# ProPrj_BEI_Kimco_Magnetic_Cylindrical_Fr.net
KiCad netlist of a schematic drawn in EasyEDA Pro
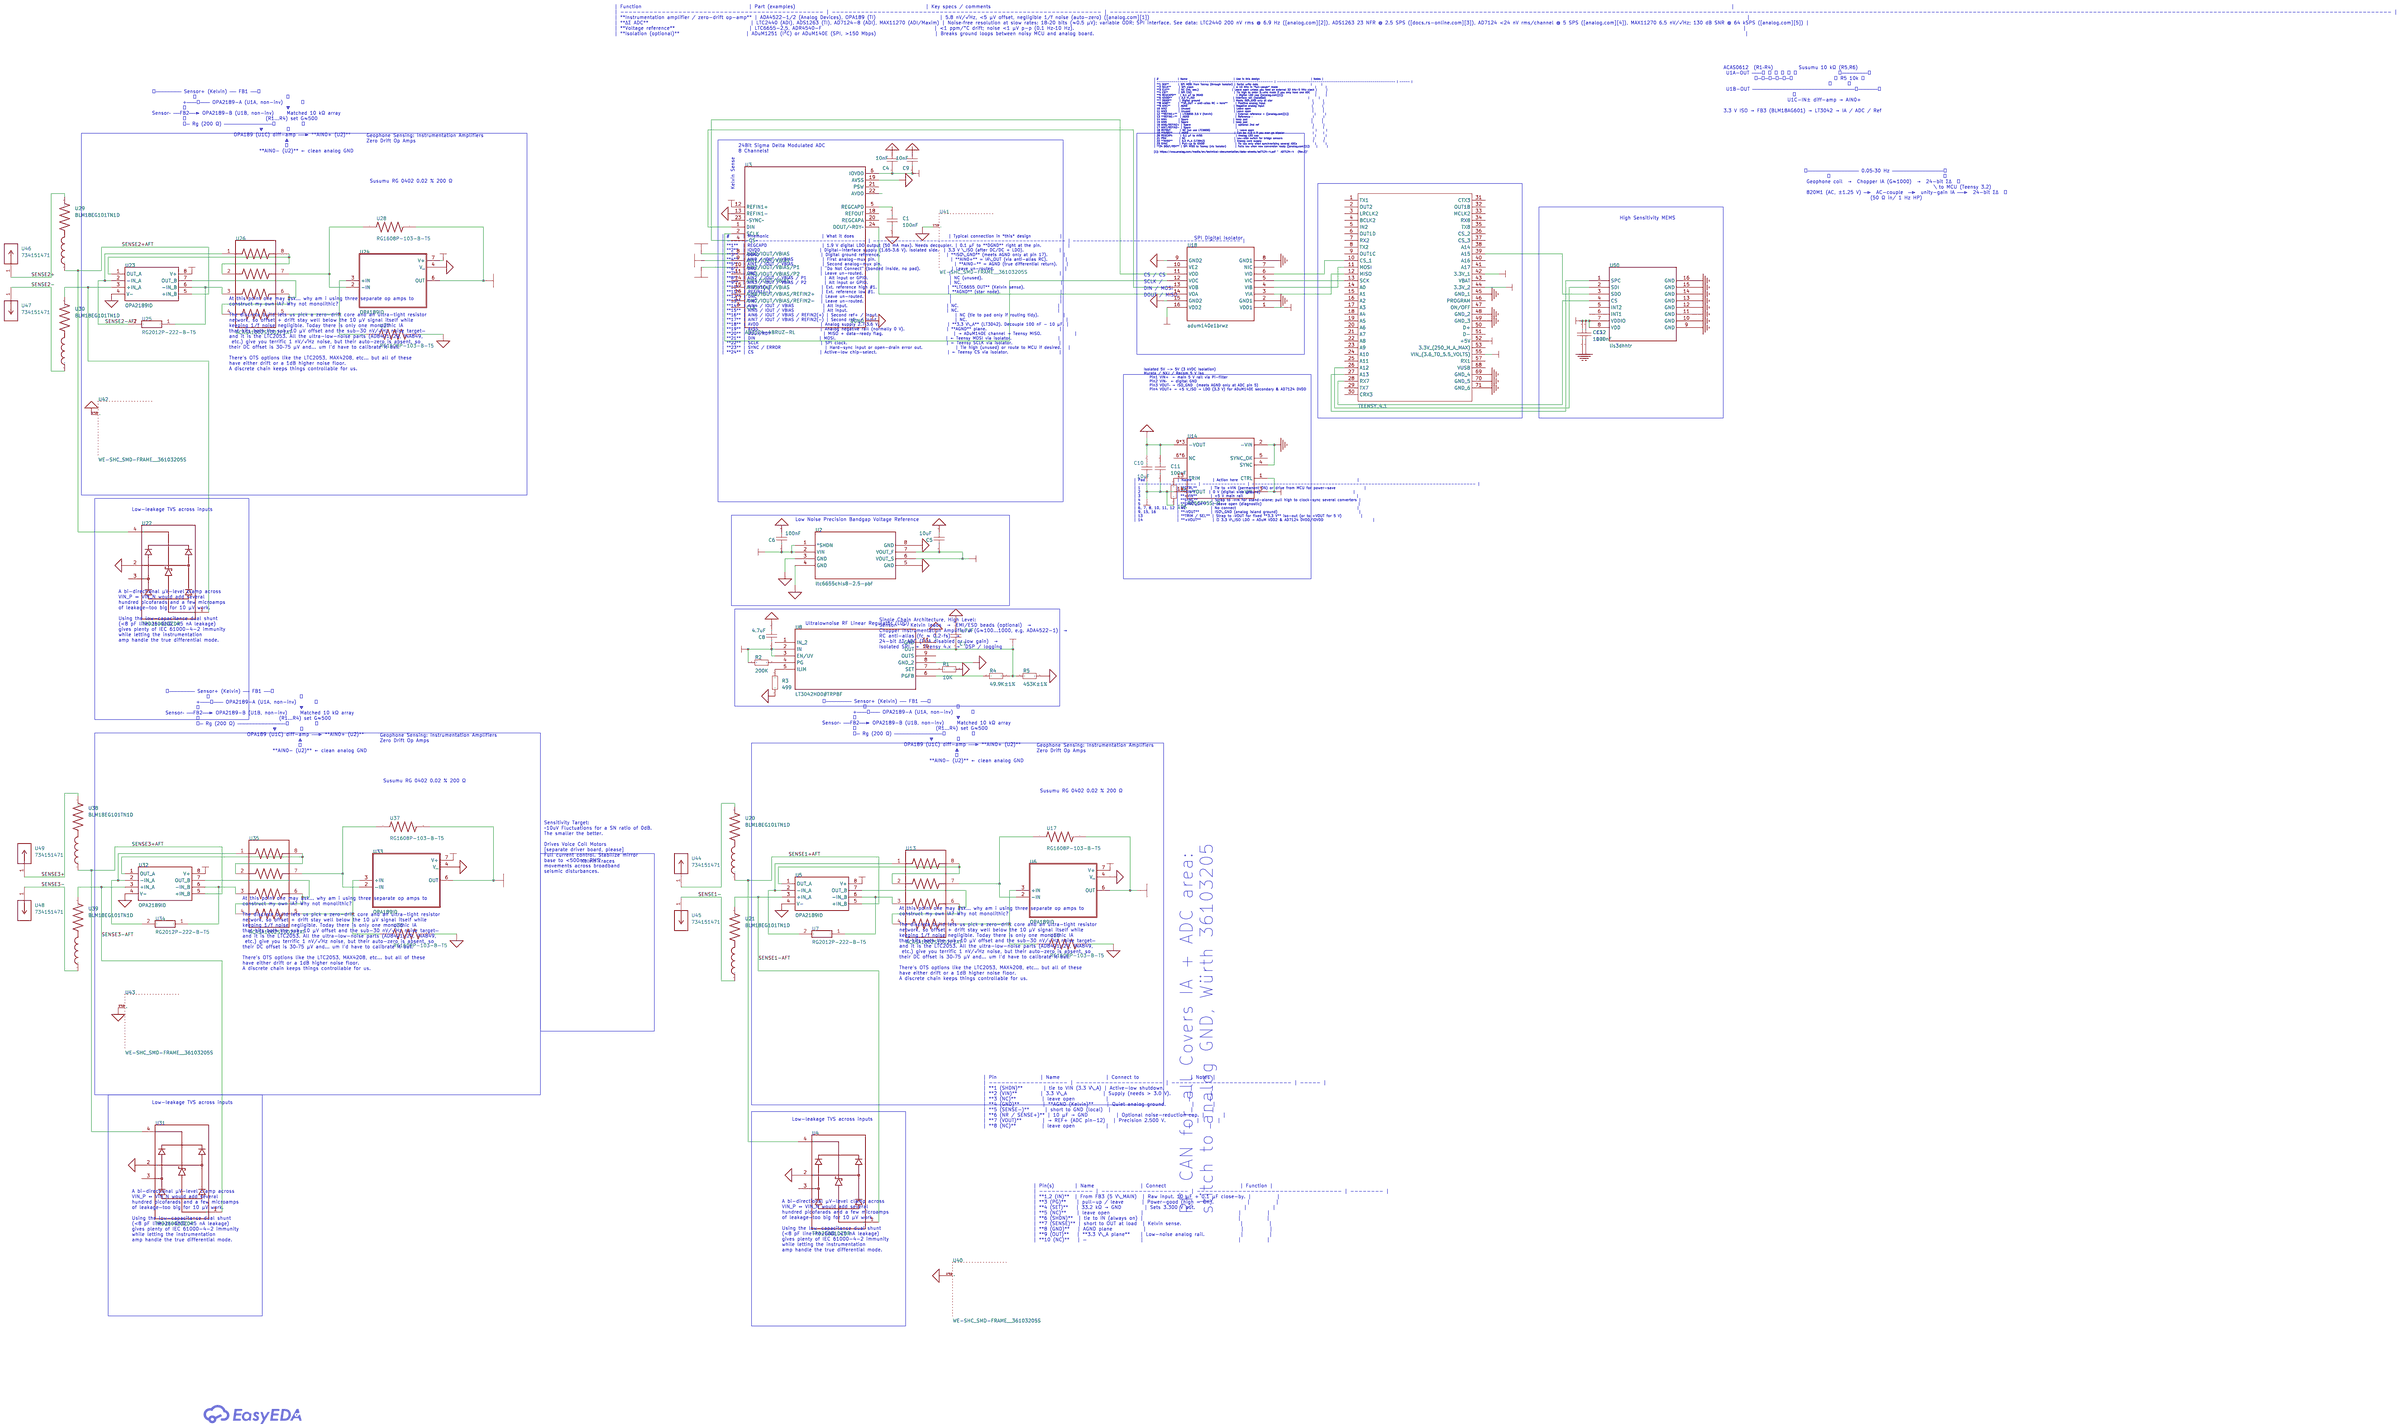
[diagram p0: schematic sheet]

(export (version "E")
  (design (tool "Eeschema 10.0.6"))
  (components
    (comp (ref "C1")
      (value "100nF")
      (footprint "easyedapro:C0603")
      (libsource (lib "easyedapro") (part "CapAcitance"))
    )
    (comp (ref "C4")
      (value "10nF")
      (footprint "easyedapro:C0603")
      (libsource (lib "easyedapro") (part "CapAcitance"))
    )
    (comp (ref "C5")
      (value "10uF")
      (footprint "easyedapro:C0603")
      (libsource (lib "easyedapro") (part "CapAcitance"))
    )
    (comp (ref "C6")
      (value "100nF")
      (footprint "easyedapro:C0603")
      (libsource (lib "easyedapro") (part "CapAcitance"))
    )
    (comp (ref "C7")
      (value "4.7uF")
      (footprint "easyedapro:C0603")
      (libsource (lib "easyedapro") (part "CapAcitance"))
    )
    (comp (ref "C8")
      (value "4.7uF")
      (footprint "easyedapro:C0603")
      (libsource (lib "easyedapro") (part "CapAcitance"))
    )
    (comp (ref "C9")
      (value "10nF")
      (footprint "easyedapro:C0603")
      (libsource (lib "easyedapro") (part "CapAcitance"))
    )
    (comp (ref "C10")
      (value "10uF")
      (footprint "easyedapro:C0603")
      (libsource (lib "easyedapro") (part "CapAcitance"))
    )
    (comp (ref "C11")
      (value "100nF")
      (footprint "easyedapro:C0603")
      (libsource (lib "easyedapro") (part "CapAcitance"))
    )
    (comp (ref "C12")
      (value "100nF")
      (footprint "easyedapro:C0603")
      (libsource (lib "easyedapro") (part "CapAcitance"))
    )
    (comp (ref "C13")
      (value "10uF")
      (footprint "easyedapro:C0603")
      (libsource (lib "easyedapro") (part "CapAcitance"))
    )
    (comp (ref "R1") (value "10K") (footprint "easyedapro:R0603") (libsource (lib "easyedapro") (part "电阻")))
    (comp (ref "R2") (value "200K") (footprint "easyedapro:R0603") (libsource (lib "easyedapro") (part "电阻")))
    (comp (ref "R3") (value "499") (footprint "easyedapro:R0603") (libsource (lib "easyedapro") (part "电阻")))
    (comp (ref "R4")
      (value "49.9K±1%")
      (footprint "easyedapro:R0603")
      (libsource (lib "easyedapro") (part "电阻"))
    )
    (comp (ref "R5")
      (value "453K±1%")
      (footprint "easyedapro:R0603")
      (libsource (lib "easyedapro") (part "电阻"))
    )
    (comp (ref "R6") (value "10K") (footprint "easyedapro:R0603") (libsource (lib "easyedapro") (part "电阻")))
    (comp (ref "U2")
      (value "ltc6655chls8-2.5-pbf")
      (footprint "easyedapro:LTC6655CHLS8-2.5-PBF")
      (libsource (lib "easyedapro") (part "ltc6655chls8-2.5-pbf"))
    )
    (comp (ref "U3")
      (value "AD7124-4BRUZ-RL")
      (footprint "easyedapro:SOP65P640X120-24N")
      (libsource (lib "easyedapro") (part "AD7124-4BRUZ-RL"))
    )
    (comp (ref "U4")
      (value "TPD2E001DZDR")
      (footprint "easyedapro:SOT192P237X122-4N")
      (libsource (lib "easyedapro") (part "TPD2E001DZDR"))
    )
    (comp (ref "U5")
      (value "OPA2189ID")
      (footprint "easyedapro:SOIC127P600X175-8N")
      (description "2 Op Amps in 1. Zero Drift.")
      (libsource (lib "easyedapro") (part "OPA2189ID"))
    )
    (comp (ref "U6")
      (value "OPA189ID")
      (footprint "easyedapro:SOIC127P599X175-8N")
      (libsource (lib "easyedapro") (part "OPA189ID"))
    )
    (comp (ref "U7")
      (value "RG2012P-222-B-T5")
      (footprint "easyedapro:RESC2012X50N")
      (libsource (lib "easyedapro") (part "RG2012P-222-B-T5"))
    )
    (comp (ref "U8")
      (value "LT3042HDD#TRPBF")
      (footprint "easyedapro:DFN-10_DD")
      (description "LDO")
      (libsource (lib "easyedapro") (part "LT3042HDD#TRPBF"))
    )
    (comp (ref "U13")
      (value "ACASA1002S1002P1AT")
      (footprint "easyedapro:RESCAXS80P320X150X55-8N")
      (libsource (lib "easyedapro") (part "ACASA1002S1002P1AT"))
    )
    (comp (ref "U14")
      (value "R05CT05S-R")
      (footprint "easyedapro:SOIC127P1030X265-16N")
      (description "Isolated 5 V→5 V DC/DC")
      (libsource (lib "easyedapro") (part "R05CT05S-R"))
    )
    (comp (ref "U16")
      (value "RG1608P-103-B-T5")
      (footprint "easyedapro:RESC1608X50N")
      (libsource (lib "easyedapro") (part "RG1608P-103-B-T5"))
    )
    (comp (ref "U17")
      (value "RG1608P-103-B-T5")
      (footprint "easyedapro:RESC1608X50N")
      (libsource (lib "easyedapro") (part "RG1608P-103-B-T5"))
    )
    (comp (ref "U18")
      (value "adum140e1brwz")
      (footprint "easyedapro:ADUM140E1BRWZ")
      (libsource (lib "easyedapro") (part "adum140e1brwz"))
    )
    (comp (ref "U20")
      (value "BLM18EG101TN1D")
      (footprint "easyedapro:BEADC1608X65N")
      (description "Ferrite Bead")
      (libsource (lib "easyedapro") (part "BLM18EG101TN1D"))
    )
    (comp (ref "U21")
      (value "BLM18EG101TN1D")
      (footprint "easyedapro:BEADC1608X65N")
      (description "Ferrite Bead")
      (libsource (lib "easyedapro") (part "BLM18EG101TN1D"))
    )
    (comp (ref "U22")
      (value "TPD2E001DZDR")
      (footprint "easyedapro:SOT192P237X122-4N")
      (libsource (lib "easyedapro") (part "TPD2E001DZDR"))
    )
    (comp (ref "U23")
      (value "OPA2189ID")
      (footprint "easyedapro:SOIC127P600X175-8N")
      (description "2 Op Amps in 1. Zero Drift.")
      (libsource (lib "easyedapro") (part "OPA2189ID"))
    )
    (comp (ref "U24")
      (value "OPA189ID")
      (footprint "easyedapro:SOIC127P599X175-8N")
      (libsource (lib "easyedapro") (part "OPA189ID"))
    )
    (comp (ref "U25")
      (value "RG2012P-222-B-T5")
      (footprint "easyedapro:RESC2012X50N")
      (libsource (lib "easyedapro") (part "RG2012P-222-B-T5"))
    )
    (comp (ref "U26")
      (value "ACASA1002S1002P1AT")
      (footprint "easyedapro:RESCAXS80P320X150X55-8N")
      (libsource (lib "easyedapro") (part "ACASA1002S1002P1AT"))
    )
    (comp (ref "U27")
      (value "RG1608P-103-B-T5")
      (footprint "easyedapro:RESC1608X50N")
      (libsource (lib "easyedapro") (part "RG1608P-103-B-T5"))
    )
    (comp (ref "U28")
      (value "RG1608P-103-B-T5")
      (footprint "easyedapro:RESC1608X50N")
      (libsource (lib "easyedapro") (part "RG1608P-103-B-T5"))
    )
    (comp (ref "U29")
      (value "BLM18EG101TN1D")
      (footprint "easyedapro:BEADC1608X65N")
      (description "Ferrite Bead")
      (libsource (lib "easyedapro") (part "BLM18EG101TN1D"))
    )
    (comp (ref "U30")
      (value "BLM18EG101TN1D")
      (footprint "easyedapro:BEADC1608X65N")
      (description "Ferrite Bead")
      (libsource (lib "easyedapro") (part "BLM18EG101TN1D"))
    )
    (comp (ref "U31")
      (value "TPD2E001DZDR")
      (footprint "easyedapro:SOT192P237X122-4N")
      (libsource (lib "easyedapro") (part "TPD2E001DZDR"))
    )
    (comp (ref "U32")
      (value "OPA2189ID")
      (footprint "easyedapro:SOIC127P600X175-8N")
      (description "2 Op Amps in 1. Zero Drift.")
      (libsource (lib "easyedapro") (part "OPA2189ID"))
    )
    (comp (ref "U33")
      (value "OPA189ID")
      (footprint "easyedapro:SOIC127P599X175-8N")
      (libsource (lib "easyedapro") (part "OPA189ID"))
    )
    (comp (ref "U34")
      (value "RG2012P-222-B-T5")
      (footprint "easyedapro:RESC2012X50N")
      (libsource (lib "easyedapro") (part "RG2012P-222-B-T5"))
    )
    (comp (ref "U35")
      (value "ACASA1002S1002P1AT")
      (footprint "easyedapro:RESCAXS80P320X150X55-8N")
      (libsource (lib "easyedapro") (part "ACASA1002S1002P1AT"))
    )
    (comp (ref "U36")
      (value "RG1608P-103-B-T5")
      (footprint "easyedapro:RESC1608X50N")
      (libsource (lib "easyedapro") (part "RG1608P-103-B-T5"))
    )
    (comp (ref "U37")
      (value "RG1608P-103-B-T5")
      (footprint "easyedapro:RESC1608X50N")
      (libsource (lib "easyedapro") (part "RG1608P-103-B-T5"))
    )
    (comp (ref "U38")
      (value "BLM18EG101TN1D")
      (footprint "easyedapro:BEADC1608X65N")
      (description "Ferrite Bead")
      (libsource (lib "easyedapro") (part "BLM18EG101TN1D"))
    )
    (comp (ref "U39")
      (value "BLM18EG101TN1D")
      (footprint "easyedapro:BEADC1608X65N")
      (description "Ferrite Bead")
      (libsource (lib "easyedapro") (part "BLM18EG101TN1D"))
    )
    (comp (ref "U40")
      (value "WE-SHC_SMD-FRAME__36103205S")
      (footprint "easyedapro:WE-SHC_SMD-FRAME_36103205S")
      (libsource (lib "easyedapro") (part "WE-SHC_SMD-FRAME__36103205S"))
    )
    (comp (ref "U41")
      (value "WE-SHC_SMD-FRAME__36103205S")
      (footprint "easyedapro:WE-SHC_SMD-FRAME_36103205S")
      (libsource (lib "easyedapro") (part "WE-SHC_SMD-FRAME__36103205S"))
    )
    (comp (ref "U42")
      (value "WE-SHC_SMD-FRAME__36103205S")
      (footprint "easyedapro:WE-SHC_SMD-FRAME_36103205S")
      (libsource (lib "easyedapro") (part "WE-SHC_SMD-FRAME__36103205S"))
    )
    (comp (ref "U43")
      (value "WE-SHC_SMD-FRAME__36103205S")
      (footprint "easyedapro:WE-SHC_SMD-FRAME_36103205S")
      (libsource (lib "easyedapro") (part "WE-SHC_SMD-FRAME__36103205S"))
    )
    (comp (ref "U44")
      (value "734151471")
      (footprint "easyedapro:CONN_734151471_MOL")
      (libsource (lib "easyedapro") (part "734151471"))
    )
    (comp (ref "U45")
      (value "734151471")
      (footprint "easyedapro:CONN_734151471_MOL")
      (libsource (lib "easyedapro") (part "734151471"))
    )
    (comp (ref "U46")
      (value "734151471")
      (footprint "easyedapro:CONN_734151471_MOL")
      (libsource (lib "easyedapro") (part "734151471"))
    )
    (comp (ref "U47")
      (value "734151471")
      (footprint "easyedapro:CONN_734151471_MOL")
      (libsource (lib "easyedapro") (part "734151471"))
    )
    (comp (ref "U48")
      (value "734151471")
      (footprint "easyedapro:CONN_734151471_MOL")
      (libsource (lib "easyedapro") (part "734151471"))
    )
    (comp (ref "U49")
      (value "734151471")
      (footprint "easyedapro:CONN_734151471_MOL")
      (libsource (lib "easyedapro") (part "734151471"))
    )
    (comp (ref "U50")
      (value "lis3dhhtr")
      (footprint "easyedapro:LIS3DHHTR")
      (libsource (lib "easyedapro") (part "lis3dhhtr"))
    )
    (comp (ref "U51")
      (value "TEENSY_4.1")
      (footprint "easyedapro:TEENSY41")
      (libsource (lib "easyedapro") (part "TEENSY_4.1"))
    )
  )
  (nets
    (net (code "1") (name "+2.5V") (class "Default")
      (node (ref "C5") (pin "2") (pinfunction "2_2") (pintype "input"))
      (node (ref "U2") (pin "6") (pinfunction "VOUT_S_6") (pintype "unspecified"))
      (node (ref "U2") (pin "7") (pinfunction "VOUT_F_7") (pintype "unspecified"))
      (node (ref "U3") (pin "12") (pinfunction "REFIN1+_12") (pintype "input"))
    )
    (net (code "2") (name "+3.3VANALOGSIDE") (class "Default")
      (node (ref "C4") (pin "1") (pinfunction "1_1") (pintype "input"))
      (node (ref "C6") (pin "2") (pinfunction "2_2") (pintype "input"))
      (node (ref "C7") (pin "2") (pinfunction "2_2") (pintype "input"))
      (node (ref "C9") (pin "1") (pinfunction "1_1") (pintype "input"))
      (node (ref "R4") (pin "2") (pinfunction "2_2") (pintype "input"))
      (node (ref "R5") (pin "1") (pinfunction "1_1") (pintype "input"))
      (node (ref "U18") (pin "16") (pinfunction "VDD2_16") (pintype "unspecified"))
      (node (ref "U2") (pin "1") (pinfunction "*SHDN_1") (pintype "unspecified"))
      (node (ref "U2") (pin "2") (pinfunction "VIN_2") (pintype "unspecified"))
      (node (ref "U23") (pin "8") (pinfunction "V+_8") (pintype "bidirectional"))
      (node (ref "U24") (pin "7") (pinfunction "V+_7") (pintype "unspecified"))
      (node (ref "U3") (pin "6") (pinfunction "IOVDD_6") (pintype "unspecified"))
      (node (ref "U32") (pin "8") (pinfunction "V+_8") (pintype "bidirectional"))
      (node (ref "U33") (pin "7") (pinfunction "V+_7") (pintype "unspecified"))
      (node (ref "U5") (pin "8") (pinfunction "V+_8") (pintype "bidirectional"))
      (node (ref "U6") (pin "7") (pinfunction "V+_7") (pintype "unspecified"))
      (node (ref "U8") (pin "10") (pinfunction "OUT_10") (pintype "output"))
    )
    (net (code "3") (name "+3.3V_D") (class "Default")
      (node (ref "C12") (pin "2") (pinfunction "2_2") (pintype "input"))
      (node (ref "C13") (pin "2") (pinfunction "2_2") (pintype "input"))
      (node (ref "U18") (pin "1") (pinfunction "VDD1_1") (pintype "unspecified"))
      (node (ref "U50") (pin "7") (pinfunction "VDDIO_7") (pintype "unspecified"))
      (node (ref "U50") (pin "8") (pinfunction "VDD_8") (pintype "unspecified"))
      (node (ref "U51") (pin "42") (pinfunction "3.3V_1_42") (pintype "bidirectional"))
      (node (ref "U51") (pin "44") (pinfunction "3.3V_2_44") (pintype "bidirectional"))
    )
    (net (code "4") (name "+5V_D") (class "Default")
      (node (ref "U14") (pin "1") (pinfunction "CTRL_1") (pintype "input"))
      (node (ref "U14") (pin "3") (pinfunction "+VIN_3") (pintype "input"))
      (node (ref "U51") (pin "52") (pinfunction "+5V_52") (pintype "bidirectional"))
      (node (ref "U51") (pin "55") (pinfunction "VIN_(3.6_TO_5.5_VOLTS)_55") (pintype "bidirectional"))
    )
    (net (code "5") (name "+5V_ISO") (class "Default")
      (node (ref "C10") (pin "1") (pinfunction "1_1") (pintype "input"))
      (node (ref "C11") (pin "1") (pinfunction "1_1") (pintype "input"))
      (node (ref "C8") (pin "2") (pinfunction "2_2") (pintype "input"))
      (node (ref "R2") (pin "1") (pinfunction "1_1") (pintype "input"))
      (node (ref "R6") (pin "1") (pinfunction "1_1") (pintype "input"))
      (node (ref "U14") (pin "14") (pinfunction "+VOUT_14") (pintype "output"))
      (node (ref "U8") (pin "2") (pinfunction "IN_2") (pintype "input"))
      (node (ref "U8") (pin "3") (pinfunction "EN/UV_3") (pintype "output"))
    )
    (net (code "6") (name "/SENSE1+AFT") (class "Default")
      (node (ref "U20") (pin "1") (pinfunction "1_1") (pintype "unspecified"))
      (node (ref "U4") (pin "4") (pinfunction "VCC_4") (pintype "unspecified"))
      (node (ref "U5") (pin "5") (pinfunction "+IN_B_5") (pintype "bidirectional"))
    )
    (net (code "7") (name "/SENSE1-") (class "Default")
      (node (ref "U21") (pin "1") (pinfunction "1_1") (pintype "unspecified"))
      (node (ref "U45") (pin "1") (pinfunction "1_1") (pintype "unspecified"))
    )
    (net (code "8") (name "/SENSE1-AFT") (class "Default")
      (node (ref "U21") (pin "2") (pinfunction "2_2") (pintype "unspecified"))
      (node (ref "U4") (pin "1") (pinfunction "GND_1") (pintype "unspecified"))
      (node (ref "U5") (pin "3") (pinfunction "+IN_A_3") (pintype "bidirectional"))
    )
    (net (code "9") (name "/SENSE2+") (class "Default")
      (node (ref "U29") (pin "2") (pinfunction "2_2") (pintype "unspecified"))
      (node (ref "U46") (pin "1") (pinfunction "1_1") (pintype "unspecified"))
    )
    (net (code "10") (name "/SENSE2+AFT") (class "Default")
      (node (ref "U22") (pin "4") (pinfunction "VCC_4") (pintype "unspecified"))
      (node (ref "U23") (pin "5") (pinfunction "+IN_B_5") (pintype "bidirectional"))
      (node (ref "U29") (pin "1") (pinfunction "1_1") (pintype "unspecified"))
    )
    (net (code "11") (name "/SENSE2-") (class "Default")
      (node (ref "U30") (pin "1") (pinfunction "1_1") (pintype "unspecified"))
      (node (ref "U47") (pin "1") (pinfunction "1_1") (pintype "unspecified"))
    )
    (net (code "12") (name "/SENSE2-AFT") (class "Default")
      (node (ref "U23") (pin "2") (pinfunction "-IN_A_2") (pintype "bidirectional"))
      (node (ref "U25") (pin "2") (pinfunction "2_2") (pintype "bidirectional"))
      (node (ref "U26") (pin "1") (pinfunction "1_1") (pintype "unspecified"))
    )
    (net (code "13") (name "/SENSE3+") (class "Default")
      (node (ref "U38") (pin "2") (pinfunction "2_2") (pintype "unspecified"))
      (node (ref "U49") (pin "1") (pinfunction "1_1") (pintype "unspecified"))
    )
    (net (code "14") (name "/SENSE3+AFT") (class "Default")
      (node (ref "U31") (pin "4") (pinfunction "VCC_4") (pintype "unspecified"))
      (node (ref "U32") (pin "5") (pinfunction "+IN_B_5") (pintype "bidirectional"))
      (node (ref "U38") (pin "1") (pinfunction "1_1") (pintype "unspecified"))
    )
    (net (code "15") (name "/SENSE3-") (class "Default")
      (node (ref "U39") (pin "1") (pinfunction "1_1") (pintype "unspecified"))
      (node (ref "U48") (pin "1") (pinfunction "1_1") (pintype "unspecified"))
    )
    (net (code "16") (name "/SENSE3-AFT") (class "Default")
      (node (ref "U31") (pin "1") (pinfunction "GND_1") (pintype "unspecified"))
      (node (ref "U32") (pin "3") (pinfunction "+IN_A_3") (pintype "bidirectional"))
      (node (ref "U39") (pin "2") (pinfunction "2_2") (pintype "unspecified"))
    )
    (net (code "17") (name "AGND") (class "Default")
      (node (ref "C1") (pin "2") (pinfunction "2_2") (pintype "input"))
      (node (ref "C10") (pin "2") (pinfunction "2_2") (pintype "input"))
      (node (ref "C11") (pin "2") (pinfunction "2_2") (pintype "input"))
      (node (ref "C4") (pin "2") (pinfunction "2_2") (pintype "input"))
      (node (ref "C5") (pin "1") (pinfunction "1_1") (pintype "input"))
      (node (ref "C6") (pin "1") (pinfunction "1_1") (pintype "input"))
      (node (ref "C7") (pin "1") (pinfunction "1_1") (pintype "input"))
      (node (ref "C8") (pin "1") (pinfunction "1_1") (pintype "input"))
      (node (ref "C9") (pin "2") (pinfunction "2_2") (pintype "input"))
      (node (ref "R1") (pin "2") (pinfunction "2_2") (pintype "input"))
      (node (ref "R3") (pin "1") (pinfunction "1_1") (pintype "input"))
      (node (ref "R5") (pin "2") (pinfunction "2_2") (pintype "input"))
      (node (ref "U14") (pin "9*3") (pinfunction "-VOUT_9*3") (pintype "output"))
      (node (ref "U16") (pin "2") (pinfunction "2_2") (pintype "unspecified"))
      (node (ref "U18") (pin "15") (pinfunction "GND2_15") (pintype "unspecified"))
      (node (ref "U18") (pin "9") (pinfunction "GND2_9") (pintype "unspecified"))
      (node (ref "U2") (pin "3") (pinfunction "GND_3") (pintype "unspecified"))
      (node (ref "U2") (pin "4") (pinfunction "GND_4") (pintype "unspecified"))
      (node (ref "U2") (pin "5") (pinfunction "GND_5") (pintype "unspecified"))
      (node (ref "U2") (pin "8") (pinfunction "GND_8") (pintype "unspecified"))
      (node (ref "U22") (pin "2") (pinfunction "IO1_2") (pintype "bidirectional"))
      (node (ref "U23") (pin "4") (pinfunction "V-_4") (pintype "bidirectional"))
      (node (ref "U24") (pin "4") (pinfunction "V__4") (pintype "unspecified"))
      (node (ref "U27") (pin "2") (pinfunction "2_2") (pintype "unspecified"))
      (node (ref "U3") (pin "13") (pinfunction "REFIN1-_13") (pintype "input"))
      (node (ref "U3") (pin "19") (pinfunction "AVSS_19") (pintype "unspecified"))
      (node (ref "U3") (pin "7") (pinfunction "DGND_7") (pintype "unspecified"))
      (node (ref "U31") (pin "2") (pinfunction "IO1_2") (pintype "bidirectional"))
      (node (ref "U32") (pin "4") (pinfunction "V-_4") (pintype "bidirectional"))
      (node (ref "U33") (pin "4") (pinfunction "V__4") (pintype "unspecified"))
      (node (ref "U36") (pin "2") (pinfunction "2_2") (pintype "unspecified"))
      (node (ref "U4") (pin "2") (pinfunction "IO1_2") (pintype "bidirectional"))
      (node (ref "U40") (pin "1*16") (pinfunction "GND_1*16") (pintype "unspecified"))
      (node (ref "U41") (pin "1*16") (pinfunction "GND_1*16") (pintype "unspecified"))
      (node (ref "U42") (pin "1*16") (pinfunction "GND_1*16") (pintype "unspecified"))
      (node (ref "U43") (pin "1*16") (pinfunction "GND_1*16") (pintype "unspecified"))
      (node (ref "U5") (pin "4") (pinfunction "V-_4") (pintype "bidirectional"))
      (node (ref "U6") (pin "4") (pinfunction "V__4") (pintype "unspecified"))
      (node (ref "U8") (pin "11") (pinfunction "GND_11") (pintype "unspecified"))
      (node (ref "U8") (pin "8") (pinfunction "GND_2_8") (pintype "unspecified"))
    )
    (net (code "18") (name "DGND") (class "Default")
      (node (ref "C12") (pin "1") (pinfunction "1_1") (pintype "input"))
      (node (ref "C13") (pin "1") (pinfunction "1_1") (pintype "input"))
      (node (ref "U14") (pin "2") (pinfunction "-VIN_2") (pintype "input"))
      (node (ref "U14") (pin "4") (pinfunction "SYNC_4") (pintype "input"))
      (node (ref "U18") (pin "2") (pinfunction "GND1_2") (pintype "unspecified"))
      (node (ref "U18") (pin "8") (pinfunction "GND1_8") (pintype "unspecified"))
      (node (ref "U50") (pin "10") (pinfunction "GND_10") (pintype "unspecified"))
      (node (ref "U50") (pin "11") (pinfunction "GND_11") (pintype "unspecified"))
      (node (ref "U50") (pin "12") (pinfunction "GND_12") (pintype "unspecified"))
      (node (ref "U50") (pin "13") (pinfunction "GND_13") (pintype "unspecified"))
      (node (ref "U50") (pin "14") (pinfunction "GND_14") (pintype "unspecified"))
      (node (ref "U50") (pin "15") (pinfunction "GND_15") (pintype "unspecified"))
      (node (ref "U50") (pin "16") (pinfunction "GND_16") (pintype "unspecified"))
      (node (ref "U50") (pin "9") (pinfunction "GND_9") (pintype "unspecified"))
      (node (ref "U51") (pin "45") (pinfunction "GND_1_45") (pintype "bidirectional"))
      (node (ref "U51") (pin "48") (pinfunction "GND_2_48") (pintype "bidirectional"))
      (node (ref "U51") (pin "49") (pinfunction "GND_3_49") (pintype "bidirectional"))
      (node (ref "U51") (pin "69") (pinfunction "GND_4_69") (pintype "bidirectional"))
      (node (ref "U51") (pin "70") (pinfunction "GND_5_70") (pintype "bidirectional"))
      (node (ref "U51") (pin "71") (pinfunction "GND_6_71") (pintype "bidirectional"))
    )
    (net (code "19") (name "Net-(U3-REGCAPD)") (class "Default")
      (node (ref "C1") (pin "1") (pinfunction "1_1") (pintype "input"))
      (node (ref "U3") (pin "5") (pinfunction "REGCAPD_5") (pintype "output"))
    )
    (net (code "20") (name "Net-(U5--IN_A)") (class "Default")
      (node (ref "U13") (pin "1") (pinfunction "1_1") (pintype "unspecified"))
      (node (ref "U5") (pin "2") (pinfunction "-IN_A_2") (pintype "bidirectional"))
      (node (ref "U7") (pin "2") (pinfunction "2_2") (pintype "bidirectional"))
    )
    (net (code "21") (name "Net-(U5--IN_B)") (class "Default")
      (node (ref "U13") (pin "3") (pinfunction "3_3") (pintype "unspecified"))
      (node (ref "U5") (pin "6") (pinfunction "-IN_B_6") (pintype "bidirectional"))
      (node (ref "U7") (pin "1") (pinfunction "1_1") (pintype "bidirectional"))
    )
    (net (code "22") (name "Net-(U5-OUT_A)") (class "Default")
      (node (ref "U13") (pin "2") (pinfunction "2_2") (pintype "unspecified"))
      (node (ref "U13") (pin "8") (pinfunction "8_8") (pintype "unspecified"))
      (node (ref "U5") (pin "1") (pinfunction "OUT_A_1") (pintype "bidirectional"))
    )
    (net (code "23") (name "Net-(U5-OUT_B)") (class "Default")
      (node (ref "U13") (pin "4") (pinfunction "4_4") (pintype "unspecified"))
      (node (ref "U13") (pin "6") (pinfunction "6_6") (pintype "unspecified"))
      (node (ref "U5") (pin "7") (pinfunction "OUT_B_7") (pintype "bidirectional"))
    )
    (net (code "24") (name "Net-(U6-+IN)") (class "Default")
      (node (ref "U13") (pin "5") (pinfunction "5_5") (pintype "unspecified"))
      (node (ref "U16") (pin "1") (pinfunction "1_1") (pintype "unspecified"))
      (node (ref "U6") (pin "3") (pinfunction "+IN_3") (pintype "input"))
    )
    (net (code "25") (name "Net-(U6--IN)") (class "Default")
      (node (ref "U13") (pin "7") (pinfunction "7_7") (pintype "unspecified"))
      (node (ref "U17") (pin "1") (pinfunction "1_1") (pintype "unspecified"))
      (node (ref "U6") (pin "2") (pinfunction "-IN_2") (pintype "input"))
    )
    (net (code "26") (name "Net-(U8-ILIM)") (class "Default")
      (node (ref "R3") (pin "2") (pinfunction "2_2") (pintype "input"))
      (node (ref "U8") (pin "5") (pinfunction "ILIM_5") (pintype "unspecified"))
    )
    (net (code "27") (name "Net-(U8-PG)") (class "Default")
      (node (ref "R2") (pin "2") (pinfunction "2_2") (pintype "input"))
      (node (ref "U8") (pin "4") (pinfunction "PG_4") (pintype "unspecified"))
    )
    (net (code "28") (name "Net-(U8-PGFB)") (class "Default")
      (node (ref "R4") (pin "1") (pinfunction "1_1") (pintype "input"))
      (node (ref "U8") (pin "6") (pinfunction "PGFB_6") (pintype "unspecified"))
    )
    (net (code "29") (name "Net-(U8-SET)") (class "Default")
      (node (ref "R1") (pin "1") (pinfunction "1_1") (pintype "input"))
      (node (ref "U8") (pin "7") (pinfunction "SET_7") (pintype "input"))
    )
    (net (code "30") (name "Net-(U14-TRIM)") (class "Default")
      (node (ref "R6") (pin "2") (pinfunction "2_2") (pintype "input"))
      (node (ref "U14") (pin "13") (pinfunction "TRIM_13") (pintype "unspecified"))
    )
    (net (code "31") (name "Net-(U18-VIA)") (class "Default")
      (node (ref "U18") (pin "3") (pinfunction "VIA_3") (pintype "unspecified"))
      (node (ref "U51") (pin "12") (pinfunction "MISO_12") (pintype "bidirectional"))
    )
    (net (code "32") (name "Net-(U18-VIB)") (class "Default")
      (node (ref "U18") (pin "4") (pinfunction "VIB_4") (pintype "unspecified"))
      (node (ref "U51") (pin "11") (pinfunction "MOSI_11") (pintype "bidirectional"))
    )
    (net (code "33") (name "Net-(U18-VIC)") (class "Default")
      (node (ref "U18") (pin "5") (pinfunction "VIC_5") (pintype "unspecified"))
      (node (ref "U51") (pin "13") (pinfunction "SCK_13") (pintype "bidirectional"))
    )
    (net (code "34") (name "Net-(U18-VID)") (class "Default")
      (node (ref "U18") (pin "6") (pinfunction "VID_6") (pintype "unspecified"))
      (node (ref "U51") (pin "10") (pinfunction "CS_1_10") (pintype "bidirectional"))
    )
    (net (code "35") (name "Net-(U18-VOA)") (class "Default")
      (node (ref "U18") (pin "14") (pinfunction "VOA_14") (pintype "unspecified"))
      (node (ref "U3") (pin "24") (pinfunction "DOUT/~RDY~_24") (pintype "output"))
    )
    (net (code "36") (name "Net-(U18-VOB)") (class "Default")
      (node (ref "U18") (pin "13") (pinfunction "VOB_13") (pintype "unspecified"))
      (node (ref "U3") (pin "1") (pinfunction "DIN_1") (pintype "input"))
    )
    (net (code "37") (name "Net-(U18-VOC)") (class "Default")
      (node (ref "U18") (pin "12") (pinfunction "VOC_12") (pintype "unspecified"))
      (node (ref "U3") (pin "2") (pinfunction "SCLK_2") (pintype "input"))
    )
    (net (code "38") (name "Net-(U18-VOD)") (class "Default")
      (node (ref "U18") (pin "11") (pinfunction "VOD_11") (pintype "unspecified"))
      (node (ref "U3") (pin "4") (pinfunction "~CS~_4") (pintype "input"))
    )
    (net (code "39") (name "Net-(U20-Pad2)") (class "Default")
      (node (ref "U20") (pin "2") (pinfunction "2_2") (pintype "unspecified"))
      (node (ref "U44") (pin "1") (pinfunction "1_1") (pintype "unspecified"))
    )
    (net (code "40") (name "Net-(U22-GND)") (class "Default")
      (node (ref "U22") (pin "1") (pinfunction "GND_1") (pintype "unspecified"))
      (node (ref "U23") (pin "3") (pinfunction "+IN_A_3") (pintype "bidirectional"))
      (node (ref "U30") (pin "2") (pinfunction "2_2") (pintype "unspecified"))
    )
    (net (code "41") (name "Net-(U23--IN_B)") (class "Default")
      (node (ref "U23") (pin "6") (pinfunction "-IN_B_6") (pintype "bidirectional"))
      (node (ref "U25") (pin "1") (pinfunction "1_1") (pintype "bidirectional"))
      (node (ref "U26") (pin "3") (pinfunction "3_3") (pintype "unspecified"))
    )
    (net (code "42") (name "Net-(U23-OUT_A)") (class "Default")
      (node (ref "U23") (pin "1") (pinfunction "OUT_A_1") (pintype "bidirectional"))
      (node (ref "U26") (pin "2") (pinfunction "2_2") (pintype "unspecified"))
      (node (ref "U26") (pin "8") (pinfunction "8_8") (pintype "unspecified"))
    )
    (net (code "43") (name "Net-(U23-OUT_B)") (class "Default")
      (node (ref "U23") (pin "7") (pinfunction "OUT_B_7") (pintype "bidirectional"))
      (node (ref "U26") (pin "4") (pinfunction "4_4") (pintype "unspecified"))
      (node (ref "U26") (pin "6") (pinfunction "6_6") (pintype "unspecified"))
    )
    (net (code "44") (name "Net-(U24-+IN)") (class "Default")
      (node (ref "U24") (pin "3") (pinfunction "+IN_3") (pintype "input"))
      (node (ref "U26") (pin "5") (pinfunction "5_5") (pintype "unspecified"))
      (node (ref "U27") (pin "1") (pinfunction "1_1") (pintype "unspecified"))
    )
    (net (code "45") (name "Net-(U24--IN)") (class "Default")
      (node (ref "U24") (pin "2") (pinfunction "-IN_2") (pintype "input"))
      (node (ref "U26") (pin "7") (pinfunction "7_7") (pintype "unspecified"))
      (node (ref "U28") (pin "1") (pinfunction "1_1") (pintype "unspecified"))
    )
    (net (code "46") (name "Net-(U32--IN_A)") (class "Default")
      (node (ref "U32") (pin "2") (pinfunction "-IN_A_2") (pintype "bidirectional"))
      (node (ref "U34") (pin "2") (pinfunction "2_2") (pintype "bidirectional"))
      (node (ref "U35") (pin "1") (pinfunction "1_1") (pintype "unspecified"))
    )
    (net (code "47") (name "Net-(U32--IN_B)") (class "Default")
      (node (ref "U32") (pin "6") (pinfunction "-IN_B_6") (pintype "bidirectional"))
      (node (ref "U34") (pin "1") (pinfunction "1_1") (pintype "bidirectional"))
      (node (ref "U35") (pin "3") (pinfunction "3_3") (pintype "unspecified"))
    )
    (net (code "48") (name "Net-(U32-OUT_A)") (class "Default")
      (node (ref "U32") (pin "1") (pinfunction "OUT_A_1") (pintype "bidirectional"))
      (node (ref "U35") (pin "2") (pinfunction "2_2") (pintype "unspecified"))
      (node (ref "U35") (pin "8") (pinfunction "8_8") (pintype "unspecified"))
    )
    (net (code "49") (name "Net-(U32-OUT_B)") (class "Default")
      (node (ref "U32") (pin "7") (pinfunction "OUT_B_7") (pintype "bidirectional"))
      (node (ref "U35") (pin "4") (pinfunction "4_4") (pintype "unspecified"))
      (node (ref "U35") (pin "6") (pinfunction "6_6") (pintype "unspecified"))
    )
    (net (code "50") (name "Net-(U33-+IN)") (class "Default")
      (node (ref "U33") (pin "3") (pinfunction "+IN_3") (pintype "input"))
      (node (ref "U35") (pin "5") (pinfunction "5_5") (pintype "unspecified"))
      (node (ref "U36") (pin "1") (pinfunction "1_1") (pintype "unspecified"))
    )
    (net (code "51") (name "Net-(U33--IN)") (class "Default")
      (node (ref "U33") (pin "2") (pinfunction "-IN_2") (pintype "input"))
      (node (ref "U35") (pin "7") (pinfunction "7_7") (pintype "unspecified"))
      (node (ref "U37") (pin "1") (pinfunction "1_1") (pintype "unspecified"))
    )
    (net (code "52") (name "Net-(U50-CS)") (class "Default")
      (node (ref "U50") (pin "4") (pinfunction "CS_4") (pintype "unspecified"))
      (node (ref "U51") (pin "28") (pinfunction "RX7_28") (pintype "bidirectional"))
    )
    (net (code "53") (name "Net-(U50-SDI)") (class "Default")
      (node (ref "U50") (pin "2") (pinfunction "SDI_2") (pintype "unspecified"))
      (node (ref "U51") (pin "26") (pinfunction "A12_26") (pintype "bidirectional"))
    )
    (net (code "54") (name "Net-(U50-SDO)") (class "Default")
      (node (ref "U50") (pin "3") (pinfunction "SDO_3") (pintype "unspecified"))
      (node (ref "U51") (pin "39") (pinfunction "A15_39") (pintype "bidirectional"))
    )
    (net (code "55") (name "Net-(U50-SPC)") (class "Default")
      (node (ref "U50") (pin "1") (pinfunction "SPC_1") (pintype "unspecified"))
      (node (ref "U51") (pin "27") (pinfunction "A13_27") (pintype "bidirectional"))
    )
    (net (code "56") (name "VOUT1") (class "Default")
      (node (ref "U17") (pin "2") (pinfunction "2_2") (pintype "unspecified"))
      (node (ref "U3") (pin "8") (pinfunction "AIN0/IOUT/VBIAS_8") (pintype "bidirectional"))
      (node (ref "U6") (pin "6") (pinfunction "OUT_6") (pintype "output"))
    )
    (net (code "57") (name "VOUT2") (class "Default")
      (node (ref "U24") (pin "6") (pinfunction "OUT_6") (pintype "output"))
      (node (ref "U28") (pin "2") (pinfunction "2_2") (pintype "unspecified"))
      (node (ref "U3") (pin "9") (pinfunction "AIN1/IOUT/VBIAS_9") (pintype "bidirectional"))
    )
    (net (code "58") (name "VOUT3") (class "Default")
      (node (ref "U3") (pin "10") (pinfunction "AIN2/IOUT/VBIAS/P1_10") (pintype "bidirectional"))
      (node (ref "U33") (pin "6") (pinfunction "OUT_6") (pintype "output"))
      (node (ref "U37") (pin "2") (pinfunction "2_2") (pintype "unspecified"))
    )
    (net (code "59") (name "unconnected-(U3-AIN3{slash}IOUT{slash}VBIAS{slash}P2-Pad11)") (class "Default")
      (node (ref "U3") (pin "11") (pinfunction "AIN3/IOUT/VBIAS/P2_11") (pintype "bidirectional"))
    )
    (net (code "60") (name "unconnected-(U3-AIN4{slash}IOUT{slash}VBIAS-Pad14)") (class "Default")
      (node (ref "U3") (pin "14") (pinfunction "AIN4/IOUT/VBIAS_14") (pintype "bidirectional"))
    )
    (net (code "61") (name "unconnected-(U3-AIN5{slash}IOUT{slash}VBIAS-Pad15)") (class "Default")
      (node (ref "U3") (pin "15") (pinfunction "AIN5/IOUT/VBIAS_15") (pintype "bidirectional"))
    )
    (net (code "62") (name "unconnected-(U3-AIN6{slash}IOUT{slash}VBIAS{slash}REFIN2+-Pad16)") (class "Default")
      (node (ref "U3") (pin "16") (pinfunction "AIN6/IOUT/VBIAS/REFIN2+_16") (pintype "bidirectional"))
    )
    (net (code "63") (name "unconnected-(U3-AIN7{slash}IOUT{slash}VBIAS{slash}REFIN2--Pad17)") (class "Default")
      (node (ref "U3") (pin "17") (pinfunction "AIN7/IOUT/VBIAS/REFIN2-_17") (pintype "bidirectional"))
    )
    (net (code "64") (name "unconnected-(U3-AVDD-Pad22)") (class "Default")
      (node (ref "U3") (pin "22") (pinfunction "AVDD_22") (pintype "unspecified"))
    )
    (net (code "65") (name "unconnected-(U3-CLK-Pad3)") (class "Default")
      (node (ref "U3") (pin "3") (pinfunction "CLK_3") (pintype "bidirectional"))
    )
    (net (code "66") (name "unconnected-(U3-PSW-Pad21)") (class "Default")
      (node (ref "U3") (pin "21") (pinfunction "PSW_21") (pintype "unspecified"))
    )
    (net (code "67") (name "unconnected-(U3-REFOUT-Pad18)") (class "Default")
      (node (ref "U3") (pin "18") (pinfunction "REFOUT_18") (pintype "output"))
    )
    (net (code "68") (name "unconnected-(U3-REGCAPA-Pad20)") (class "Default")
      (node (ref "U3") (pin "20") (pinfunction "REGCAPA_20") (pintype "output"))
    )
    (net (code "69") (name "unconnected-(U3-~SYNC~-Pad23)") (class "Default")
      (node (ref "U3") (pin "23") (pinfunction "~SYNC~_23") (pintype "input"))
    )
    (net (code "70") (name "unconnected-(U4-IO2-Pad3)") (class "Default")
      (node (ref "U4") (pin "3") (pinfunction "IO2_3") (pintype "bidirectional"))
    )
    (net (code "71") (name "unconnected-(U8-IN_2-Pad1)") (class "Default")
      (node (ref "U8") (pin "1") (pinfunction "IN_2_1") (pintype "input"))
    )
    (net (code "72") (name "unconnected-(U8-OUTS-Pad9)") (class "Default")
      (node (ref "U8") (pin "9") (pinfunction "OUTS_9") (pintype "output"))
    )
    (net (code "73") (name "unconnected-(U14-NC-Pad6*6)") (class "Default")
      (node (ref "U14") (pin "6*6") (pinfunction "NC_6*6") (pintype "unspecified"))
    )
    (net (code "74") (name "unconnected-(U14-SYNC_OK-Pad5)") (class "Default")
      (node (ref "U14") (pin "5") (pinfunction "SYNC_OK_5") (pintype "input"))
    )
    (net (code "75") (name "unconnected-(U18-NIC-Pad7)") (class "Default")
      (node (ref "U18") (pin "7") (pinfunction "NIC_7") (pintype "unspecified"))
    )
    (net (code "76") (name "unconnected-(U18-VE2-Pad10)") (class "Default")
      (node (ref "U18") (pin "10") (pinfunction "VE2_10") (pintype "unspecified"))
    )
    (net (code "77") (name "unconnected-(U22-IO2-Pad3)") (class "Default")
      (node (ref "U22") (pin "3") (pinfunction "IO2_3") (pintype "bidirectional"))
    )
    (net (code "78") (name "unconnected-(U31-IO2-Pad3)") (class "Default")
      (node (ref "U31") (pin "3") (pinfunction "IO2_3") (pintype "bidirectional"))
    )
    (net (code "79") (name "unconnected-(U50-INT1-Pad6)") (class "Default")
      (node (ref "U50") (pin "6") (pinfunction "INT1_6") (pintype "unspecified"))
    )
    (net (code "80") (name "unconnected-(U50-INT2-Pad5)") (class "Default")
      (node (ref "U50") (pin "5") (pinfunction "INT2_5") (pintype "unspecified"))
    )
    (net (code "81") (name "unconnected-(U51-3.3V_(250_M_A_MAX)-Pad53)") (class "Default")
      (node (ref "U51") (pin "53") (pinfunction "3.3V_(250_M_A_MAX)_53") (pintype "bidirectional"))
    )
    (net (code "82") (name "unconnected-(U51-A0-Pad14)") (class "Default")
      (node (ref "U51") (pin "14") (pinfunction "A0_14") (pintype "bidirectional"))
    )
    (net (code "83") (name "unconnected-(U51-A1-Pad15)") (class "Default")
      (node (ref "U51") (pin "15") (pinfunction "A1_15") (pintype "bidirectional"))
    )
    (net (code "84") (name "unconnected-(U51-A2-Pad16)") (class "Default")
      (node (ref "U51") (pin "16") (pinfunction "A2_16") (pintype "bidirectional"))
    )
    (net (code "85") (name "unconnected-(U51-A3-Pad17)") (class "Default")
      (node (ref "U51") (pin "17") (pinfunction "A3_17") (pintype "bidirectional"))
    )
    (net (code "86") (name "unconnected-(U51-A4-Pad18)") (class "Default")
      (node (ref "U51") (pin "18") (pinfunction "A4_18") (pintype "bidirectional"))
    )
    (net (code "87") (name "unconnected-(U51-A5-Pad19)") (class "Default")
      (node (ref "U51") (pin "19") (pinfunction "A5_19") (pintype "bidirectional"))
    )
    (net (code "88") (name "unconnected-(U51-A6-Pad20)") (class "Default")
      (node (ref "U51") (pin "20") (pinfunction "A6_20") (pintype "bidirectional"))
    )
    (net (code "89") (name "unconnected-(U51-A7-Pad21)") (class "Default")
      (node (ref "U51") (pin "21") (pinfunction "A7_21") (pintype "bidirectional"))
    )
    (net (code "90") (name "unconnected-(U51-A8-Pad22)") (class "Default")
      (node (ref "U51") (pin "22") (pinfunction "A8_22") (pintype "bidirectional"))
    )
    (net (code "91") (name "unconnected-(U51-A9-Pad23)") (class "Default")
      (node (ref "U51") (pin "23") (pinfunction "A9_23") (pintype "bidirectional"))
    )
    (net (code "92") (name "unconnected-(U51-A10-Pad24)") (class "Default")
      (node (ref "U51") (pin "24") (pinfunction "A10_24") (pintype "bidirectional"))
    )
    (net (code "93") (name "unconnected-(U51-A11-Pad25)") (class "Default")
      (node (ref "U51") (pin "25") (pinfunction "A11_25") (pintype "bidirectional"))
    )
    (net (code "94") (name "unconnected-(U51-A14-Pad38)") (class "Default")
      (node (ref "U51") (pin "38") (pinfunction "A14_38") (pintype "bidirectional"))
    )
    (net (code "95") (name "unconnected-(U51-A16-Pad40)") (class "Default")
      (node (ref "U51") (pin "40") (pinfunction "A16_40") (pintype "bidirectional"))
    )
    (net (code "96") (name "unconnected-(U51-A17-Pad41)") (class "Default")
      (node (ref "U51") (pin "41") (pinfunction "A17_41") (pintype "bidirectional"))
    )
    (net (code "97") (name "unconnected-(U51-BCLK2-Pad4)") (class "Default")
      (node (ref "U51") (pin "4") (pinfunction "BCLK2_4") (pintype "bidirectional"))
    )
    (net (code "98") (name "unconnected-(U51-CRX3-Pad30)") (class "Default")
      (node (ref "U51") (pin "30") (pinfunction "CRX3_30") (pintype "bidirectional"))
    )
    (net (code "99") (name "unconnected-(U51-CS_2-Pad36)") (class "Default")
      (node (ref "U51") (pin "36") (pinfunction "CS_2_36") (pintype "bidirectional"))
    )
    (net (code "100") (name "unconnected-(U51-CS_3-Pad37)") (class "Default")
      (node (ref "U51") (pin "37") (pinfunction "CS_3_37") (pintype "bidirectional"))
    )
    (net (code "101") (name "unconnected-(U51-CTX3-Pad31)") (class "Default")
      (node (ref "U51") (pin "31") (pinfunction "CTX3_31") (pintype "bidirectional"))
    )
    (net (code "102") (name "unconnected-(U51-D+-Pad50)") (class "Default")
      (node (ref "U51") (pin "50") (pinfunction "D+_50") (pintype "bidirectional"))
    )
    (net (code "103") (name "unconnected-(U51-D--Pad51)") (class "Default")
      (node (ref "U51") (pin "51") (pinfunction "D-_51") (pintype "bidirectional"))
    )
    (net (code "104") (name "unconnected-(U51-IN2-Pad5)") (class "Default")
      (node (ref "U51") (pin "5") (pinfunction "IN2_5") (pintype "bidirectional"))
    )
    (net (code "105") (name "unconnected-(U51-LRCLK2-Pad3)") (class "Default")
      (node (ref "U51") (pin "3") (pinfunction "LRCLK2_3") (pintype "bidirectional"))
    )
    (net (code "106") (name "unconnected-(U51-MCLK2-Pad33)") (class "Default")
      (node (ref "U51") (pin "33") (pinfunction "MCLK2_33") (pintype "bidirectional"))
    )
    (net (code "107") (name "unconnected-(U51-ON{slash}OFF-Pad47)") (class "Default")
      (node (ref "U51") (pin "47") (pinfunction "ON/OFF_47") (pintype "bidirectional"))
    )
    (net (code "108") (name "unconnected-(U51-OUT1B-Pad32)") (class "Default")
      (node (ref "U51") (pin "32") (pinfunction "OUT1B_32") (pintype "bidirectional"))
    )
    (net (code "109") (name "unconnected-(U51-OUT1C-Pad9)") (class "Default")
      (node (ref "U51") (pin "9") (pinfunction "OUT1C_9") (pintype "bidirectional"))
    )
    (net (code "110") (name "unconnected-(U51-OUT1D-Pad6)") (class "Default")
      (node (ref "U51") (pin "6") (pinfunction "OUT1D_6") (pintype "bidirectional"))
    )
    (net (code "111") (name "unconnected-(U51-OUT2-Pad2)") (class "Default")
      (node (ref "U51") (pin "2") (pinfunction "OUT2_2") (pintype "bidirectional"))
    )
    (net (code "112") (name "unconnected-(U51-PROGRAM-Pad46)") (class "Default")
      (node (ref "U51") (pin "46") (pinfunction "PROGRAM_46") (pintype "bidirectional"))
    )
    (net (code "113") (name "unconnected-(U51-RX1-Pad57)") (class "Default")
      (node (ref "U51") (pin "57") (pinfunction "RX1_57") (pintype "bidirectional"))
    )
    (net (code "114") (name "unconnected-(U51-RX2-Pad7)") (class "Default")
      (node (ref "U51") (pin "7") (pinfunction "RX2_7") (pintype "bidirectional"))
    )
    (net (code "115") (name "unconnected-(U51-RX8-Pad34)") (class "Default")
      (node (ref "U51") (pin "34") (pinfunction "RX8_34") (pintype "bidirectional"))
    )
    (net (code "116") (name "unconnected-(U51-TX1-Pad1)") (class "Default")
      (node (ref "U51") (pin "1") (pinfunction "TX1_1") (pintype "bidirectional"))
    )
    (net (code "117") (name "unconnected-(U51-TX2-Pad8)") (class "Default")
      (node (ref "U51") (pin "8") (pinfunction "TX2_8") (pintype "bidirectional"))
    )
    (net (code "118") (name "unconnected-(U51-TX7-Pad29)") (class "Default")
      (node (ref "U51") (pin "29") (pinfunction "TX7_29") (pintype "bidirectional"))
    )
    (net (code "119") (name "unconnected-(U51-TX8-Pad35)") (class "Default")
      (node (ref "U51") (pin "35") (pinfunction "TX8_35") (pintype "bidirectional"))
    )
    (net (code "120") (name "unconnected-(U51-VBAT-Pad43)") (class "Default")
      (node (ref "U51") (pin "43") (pinfunction "VBAT_43") (pintype "bidirectional"))
    )
    (net (code "121") (name "unconnected-(U51-VUSB-Pad68)") (class "Default")
      (node (ref "U51") (pin "68") (pinfunction "VUSB_68") (pintype "bidirectional"))
    )
  )
)
